# DAC.net
KiCad netlist of a schematic drawn in Altium Designer
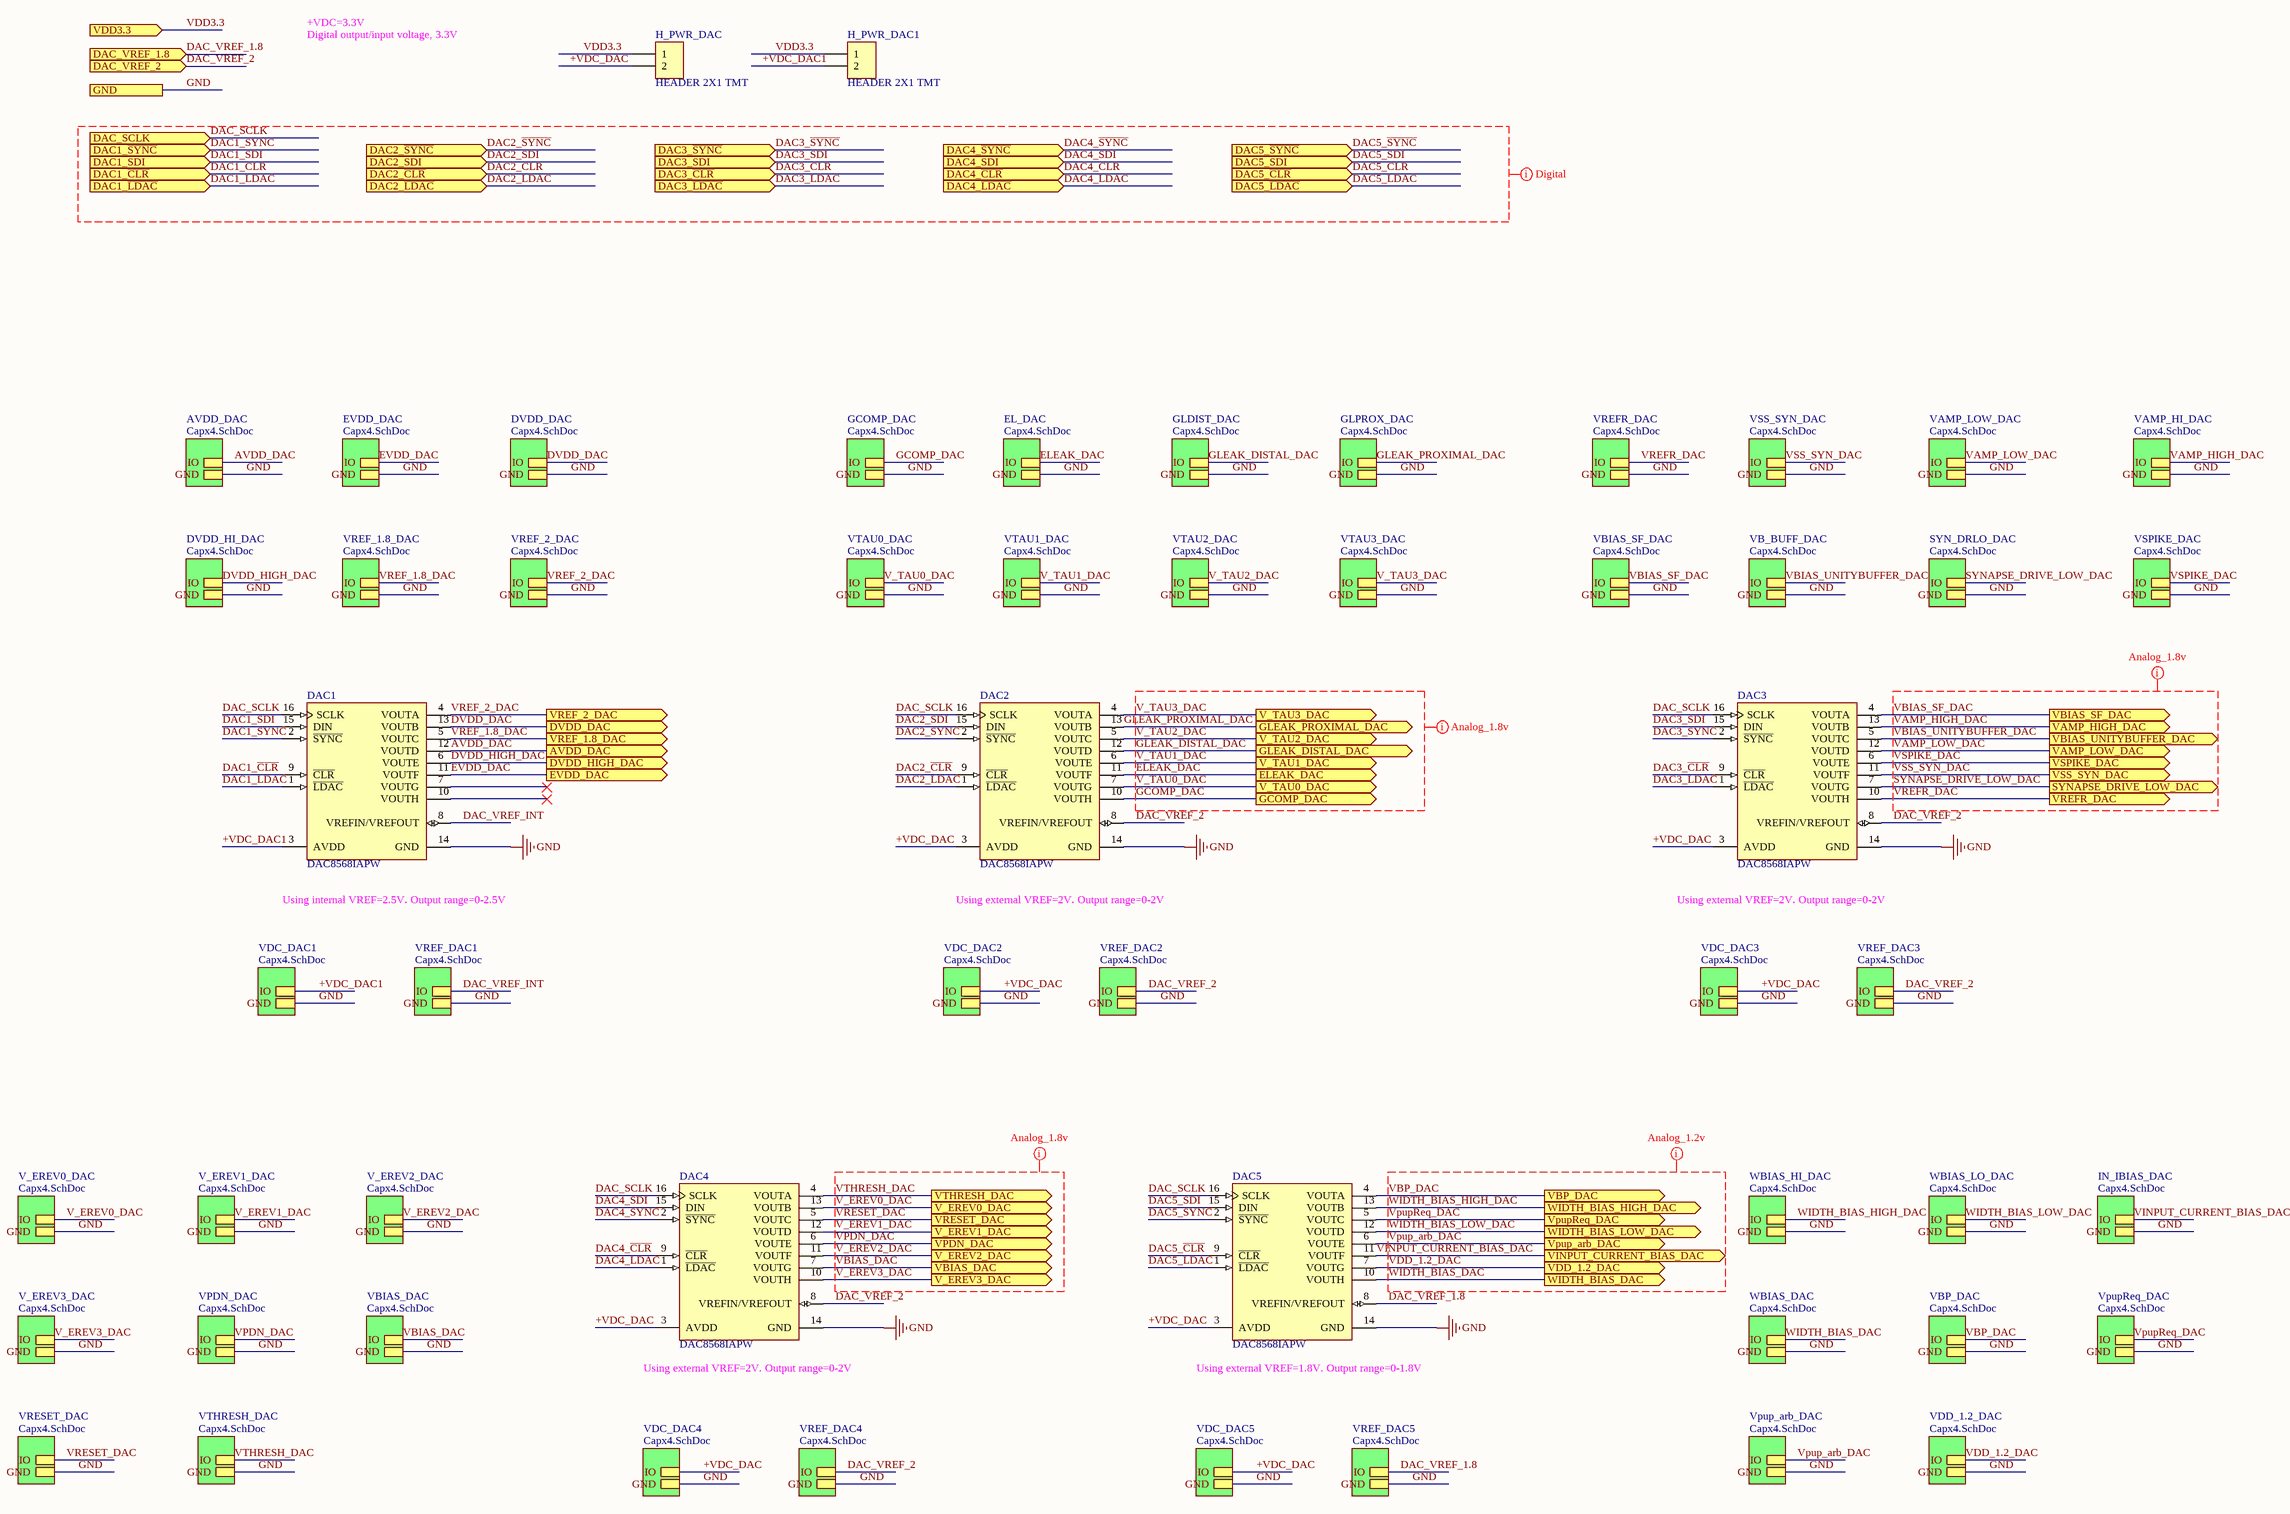
[diagram p0: DAC.SchDoc]

(export (version "E")
  (design (tool "Eeschema 10.0.6"))
  (components
    (comp (ref "DAC1")
      (value "DAC8568IAPW")
      (footprint "TI-PW16_M")
      (fields (field (name "MANUFACTURER") "Texas Instruments"))
      (libsource (lib "Altium Content Vault") (part "TI-DAC8568PW16"))
    )
    (comp (ref "DAC2")
      (value "DAC8568IAPW")
      (footprint "TI-PW16_M")
      (fields (field (name "MANUFACTURER") "Texas Instruments"))
      (libsource (lib "Altium Content Vault") (part "TI-DAC8568PW16"))
    )
    (comp (ref "DAC3")
      (value "DAC8568IAPW")
      (footprint "TI-PW16_M")
      (fields (field (name "MANUFACTURER") "Texas Instruments"))
      (libsource (lib "Altium Content Vault") (part "TI-DAC8568PW16"))
    )
    (comp (ref "DAC4")
      (value "DAC8568IAPW")
      (footprint "TI-PW16_M")
      (fields (field (name "MANUFACTURER") "Texas Instruments"))
      (libsource (lib "Altium Content Vault") (part "TI-DAC8568PW16"))
    )
    (comp (ref "DAC5")
      (value "DAC8568IAPW")
      (footprint "TI-PW16_M")
      (fields (field (name "MANUFACTURER") "Texas Instruments"))
      (libsource (lib "Altium Content Vault") (part "TI-DAC8568PW16"))
    )
    (comp (ref "H_PWR_DAC")
      (value "HEADER 2X1 TMT")
      (footprint "MRI_ADC:Samtec TSW-102-07-G-S")
      (description "CONN HEADER VERT 2POS 2.54MM\r\nConnector Header Through Hole 2 position 0.100\" (2.54mm)")
      (libsource (lib "MRI_ADC") (part "HEADER 2X1 TMT"))
    )
    (comp (ref "H_PWR_DAC1")
      (value "HEADER 2X1 TMT")
      (footprint "MRI_ADC:Samtec TSW-102-07-G-S")
      (description "CONN HEADER VERT 2POS 2.54MM\r\nConnector Header Through Hole 2 position 0.100\" (2.54mm)")
      (libsource (lib "MRI_ADC") (part "HEADER 2X1 TMT"))
    )
  )
  (nets
    (net (code "1") (name "/+VDC_DAC") (class "Default")
      (node (ref "DAC2") (pin "3") (pinfunction "AVDD_3") (pintype "power_in"))
      (node (ref "DAC3") (pin "3") (pinfunction "AVDD_3") (pintype "power_in"))
      (node (ref "DAC4") (pin "3") (pinfunction "AVDD_3") (pintype "power_in"))
      (node (ref "DAC5") (pin "3") (pinfunction "AVDD_3") (pintype "power_in"))
      (node (ref "H_PWR_DAC") (pin "2") (pinfunction "2_2") (pintype "passive"))
    )
    (net (code "2") (name "/+VDC_DAC1") (class "Default")
      (node (ref "DAC1") (pin "3") (pinfunction "AVDD_3") (pintype "power_in"))
      (node (ref "H_PWR_DAC1") (pin "2") (pinfunction "2_2") (pintype "passive"))
    )
    (net (code "3") (name "/AVDD_DAC") (class "Default")
      (node (ref "DAC1") (pin "12") (pinfunction "VOUTD_12") (pintype "tri_state"))
    )
    (net (code "4") (name "/DAC1_SDI") (class "Default")
      (node (ref "DAC1") (pin "15") (pinfunction "DIN_15") (pintype "input"))
    )
    (net (code "5") (name "/DAC1_~{CLR}") (class "Default")
      (node (ref "DAC1") (pin "9") (pinfunction "~{CLR}_9") (pintype "input"))
    )
    (net (code "6") (name "/DAC1_~{LDAC}") (class "Default")
      (node (ref "DAC1") (pin "1") (pinfunction "~{LDAC}_1") (pintype "input"))
    )
    (net (code "7") (name "/DAC1_~{SYNC}") (class "Default")
      (node (ref "DAC1") (pin "2") (pinfunction "~{SYNC}_2") (pintype "input"))
    )
    (net (code "8") (name "/DAC2_SDI") (class "Default")
      (node (ref "DAC2") (pin "15") (pinfunction "DIN_15") (pintype "input"))
    )
    (net (code "9") (name "/DAC2_~{CLR}") (class "Default")
      (node (ref "DAC2") (pin "9") (pinfunction "~{CLR}_9") (pintype "input"))
    )
    (net (code "10") (name "/DAC2_~{LDAC}") (class "Default")
      (node (ref "DAC2") (pin "1") (pinfunction "~{LDAC}_1") (pintype "input"))
    )
    (net (code "11") (name "/DAC2_~{SYNC}") (class "Default")
      (node (ref "DAC2") (pin "2") (pinfunction "~{SYNC}_2") (pintype "input"))
    )
    (net (code "12") (name "/DAC3_SDI") (class "Default")
      (node (ref "DAC3") (pin "15") (pinfunction "DIN_15") (pintype "input"))
    )
    (net (code "13") (name "/DAC3_~{CLR}") (class "Default")
      (node (ref "DAC3") (pin "9") (pinfunction "~{CLR}_9") (pintype "input"))
    )
    (net (code "14") (name "/DAC3_~{LDAC}") (class "Default")
      (node (ref "DAC3") (pin "1") (pinfunction "~{LDAC}_1") (pintype "input"))
    )
    (net (code "15") (name "/DAC3_~{SYNC}") (class "Default")
      (node (ref "DAC3") (pin "2") (pinfunction "~{SYNC}_2") (pintype "input"))
    )
    (net (code "16") (name "/DAC4_SDI") (class "Default")
      (node (ref "DAC4") (pin "15") (pinfunction "DIN_15") (pintype "input"))
    )
    (net (code "17") (name "/DAC4_~{CLR}") (class "Default")
      (node (ref "DAC4") (pin "9") (pinfunction "~{CLR}_9") (pintype "input"))
    )
    (net (code "18") (name "/DAC4_~{LDAC}") (class "Default")
      (node (ref "DAC4") (pin "1") (pinfunction "~{LDAC}_1") (pintype "input"))
    )
    (net (code "19") (name "/DAC4_~{SYNC}") (class "Default")
      (node (ref "DAC4") (pin "2") (pinfunction "~{SYNC}_2") (pintype "input"))
    )
    (net (code "20") (name "/DAC5_SDI") (class "Default")
      (node (ref "DAC5") (pin "15") (pinfunction "DIN_15") (pintype "input"))
    )
    (net (code "21") (name "/DAC5_~{CLR}") (class "Default")
      (node (ref "DAC5") (pin "9") (pinfunction "~{CLR}_9") (pintype "input"))
    )
    (net (code "22") (name "/DAC5_~{LDAC}") (class "Default")
      (node (ref "DAC5") (pin "1") (pinfunction "~{LDAC}_1") (pintype "input"))
    )
    (net (code "23") (name "/DAC5_~{SYNC}") (class "Default")
      (node (ref "DAC5") (pin "2") (pinfunction "~{SYNC}_2") (pintype "input"))
    )
    (net (code "24") (name "/DAC_SCLK") (class "Default")
      (node (ref "DAC1") (pin "16") (pinfunction "SCLK_16") (pintype "input"))
      (node (ref "DAC2") (pin "16") (pinfunction "SCLK_16") (pintype "input"))
      (node (ref "DAC3") (pin "16") (pinfunction "SCLK_16") (pintype "input"))
      (node (ref "DAC4") (pin "16") (pinfunction "SCLK_16") (pintype "input"))
      (node (ref "DAC5") (pin "16") (pinfunction "SCLK_16") (pintype "input"))
    )
    (net (code "25") (name "/DAC_VREF_1.8") (class "Default")
      (node (ref "DAC5") (pin "8") (pinfunction "VREFIN/VREFOUT_8") (pintype "bidirectional"))
    )
    (net (code "26") (name "/DAC_VREF_2") (class "Default")
      (node (ref "DAC2") (pin "8") (pinfunction "VREFIN/VREFOUT_8") (pintype "bidirectional"))
      (node (ref "DAC3") (pin "8") (pinfunction "VREFIN/VREFOUT_8") (pintype "bidirectional"))
      (node (ref "DAC4") (pin "8") (pinfunction "VREFIN/VREFOUT_8") (pintype "bidirectional"))
    )
    (net (code "27") (name "/DAC_VREF_INT") (class "Default")
      (node (ref "DAC1") (pin "8") (pinfunction "VREFIN/VREFOUT_8") (pintype "bidirectional"))
    )
    (net (code "28") (name "/DVDD_DAC") (class "Default")
      (node (ref "DAC1") (pin "13") (pinfunction "VOUTB_13") (pintype "tri_state"))
    )
    (net (code "29") (name "/DVDD_HIGH_DAC") (class "Default")
      (node (ref "DAC1") (pin "6") (pinfunction "VOUTE_6") (pintype "tri_state"))
    )
    (net (code "30") (name "/ELEAK_DAC") (class "Default")
      (node (ref "DAC2") (pin "11") (pinfunction "VOUTF_11") (pintype "tri_state"))
    )
    (net (code "31") (name "/EVDD_DAC") (class "Default")
      (node (ref "DAC1") (pin "11") (pinfunction "VOUTF_11") (pintype "tri_state"))
    )
    (net (code "32") (name "/GCOMP_DAC") (class "Default")
      (node (ref "DAC2") (pin "10") (pinfunction "VOUTH_10") (pintype "tri_state"))
    )
    (net (code "33") (name "/GLEAK_DISTAL_DAC") (class "Default")
      (node (ref "DAC2") (pin "12") (pinfunction "VOUTD_12") (pintype "tri_state"))
    )
    (net (code "34") (name "/GLEAK_PROXIMAL_DAC") (class "Default")
      (node (ref "DAC2") (pin "13") (pinfunction "VOUTB_13") (pintype "tri_state"))
    )
    (net (code "35") (name "/SYNAPSE_DRIVE_LOW_DAC") (class "Default")
      (node (ref "DAC3") (pin "7") (pinfunction "VOUTG_7") (pintype "tri_state"))
    )
    (net (code "36") (name "/VAMP_HIGH_DAC") (class "Default")
      (node (ref "DAC3") (pin "13") (pinfunction "VOUTB_13") (pintype "tri_state"))
    )
    (net (code "37") (name "/VAMP_LOW_DAC") (class "Default")
      (node (ref "DAC3") (pin "12") (pinfunction "VOUTD_12") (pintype "tri_state"))
    )
    (net (code "38") (name "/VBIAS_DAC") (class "Default")
      (node (ref "DAC4") (pin "7") (pinfunction "VOUTG_7") (pintype "tri_state"))
    )
    (net (code "39") (name "/VBIAS_SF_DAC") (class "Default")
      (node (ref "DAC3") (pin "4") (pinfunction "VOUTA_4") (pintype "tri_state"))
    )
    (net (code "40") (name "/VBIAS_UNITYBUFFER_DAC") (class "Default")
      (node (ref "DAC3") (pin "5") (pinfunction "VOUTC_5") (pintype "tri_state"))
    )
    (net (code "41") (name "/VBP_DAC") (class "Default")
      (node (ref "DAC5") (pin "4") (pinfunction "VOUTA_4") (pintype "tri_state"))
    )
    (net (code "42") (name "/VDD3.3") (class "Default")
      (node (ref "H_PWR_DAC") (pin "1") (pinfunction "1_1") (pintype "passive"))
      (node (ref "H_PWR_DAC1") (pin "1") (pinfunction "1_1") (pintype "passive"))
    )
    (net (code "43") (name "/VDD_1.2_DAC") (class "Default")
      (node (ref "DAC5") (pin "7") (pinfunction "VOUTG_7") (pintype "tri_state"))
    )
    (net (code "44") (name "/VINPUT_CURRENT_BIAS_DAC") (class "Default")
      (node (ref "DAC5") (pin "11") (pinfunction "VOUTF_11") (pintype "tri_state"))
    )
    (net (code "45") (name "/VPDN_DAC") (class "Default")
      (node (ref "DAC4") (pin "6") (pinfunction "VOUTE_6") (pintype "tri_state"))
    )
    (net (code "46") (name "/VREFR_DAC") (class "Default")
      (node (ref "DAC3") (pin "10") (pinfunction "VOUTH_10") (pintype "tri_state"))
    )
    (net (code "47") (name "/VREF_1.8_DAC") (class "Default")
      (node (ref "DAC1") (pin "5") (pinfunction "VOUTC_5") (pintype "tri_state"))
    )
    (net (code "48") (name "/VREF_2_DAC") (class "Default")
      (node (ref "DAC1") (pin "4") (pinfunction "VOUTA_4") (pintype "tri_state"))
    )
    (net (code "49") (name "/VRESET_DAC") (class "Default")
      (node (ref "DAC4") (pin "5") (pinfunction "VOUTC_5") (pintype "tri_state"))
    )
    (net (code "50") (name "/VSPIKE_DAC") (class "Default")
      (node (ref "DAC3") (pin "6") (pinfunction "VOUTE_6") (pintype "tri_state"))
    )
    (net (code "51") (name "/VSS_SYN_DAC") (class "Default")
      (node (ref "DAC3") (pin "11") (pinfunction "VOUTF_11") (pintype "tri_state"))
    )
    (net (code "52") (name "/VTHRESH_DAC") (class "Default")
      (node (ref "DAC4") (pin "4") (pinfunction "VOUTA_4") (pintype "tri_state"))
    )
    (net (code "53") (name "/V_EREV0_DAC") (class "Default")
      (node (ref "DAC4") (pin "13") (pinfunction "VOUTB_13") (pintype "tri_state"))
    )
    (net (code "54") (name "/V_EREV1_DAC") (class "Default")
      (node (ref "DAC4") (pin "12") (pinfunction "VOUTD_12") (pintype "tri_state"))
    )
    (net (code "55") (name "/V_EREV2_DAC") (class "Default")
      (node (ref "DAC4") (pin "11") (pinfunction "VOUTF_11") (pintype "tri_state"))
    )
    (net (code "56") (name "/V_EREV3_DAC") (class "Default")
      (node (ref "DAC4") (pin "10") (pinfunction "VOUTH_10") (pintype "tri_state"))
    )
    (net (code "57") (name "/V_TAU0_DAC") (class "Default")
      (node (ref "DAC2") (pin "7") (pinfunction "VOUTG_7") (pintype "tri_state"))
    )
    (net (code "58") (name "/V_TAU1_DAC") (class "Default")
      (node (ref "DAC2") (pin "6") (pinfunction "VOUTE_6") (pintype "tri_state"))
    )
    (net (code "59") (name "/V_TAU2_DAC") (class "Default")
      (node (ref "DAC2") (pin "5") (pinfunction "VOUTC_5") (pintype "tri_state"))
    )
    (net (code "60") (name "/V_TAU3_DAC") (class "Default")
      (node (ref "DAC2") (pin "4") (pinfunction "VOUTA_4") (pintype "tri_state"))
    )
    (net (code "61") (name "/VpupReq_DAC") (class "Default")
      (node (ref "DAC5") (pin "5") (pinfunction "VOUTC_5") (pintype "tri_state"))
    )
    (net (code "62") (name "/Vpup_arb_DAC") (class "Default")
      (node (ref "DAC5") (pin "6") (pinfunction "VOUTE_6") (pintype "tri_state"))
    )
    (net (code "63") (name "/WIDTH_BIAS_DAC") (class "Default")
      (node (ref "DAC5") (pin "10") (pinfunction "VOUTH_10") (pintype "tri_state"))
    )
    (net (code "64") (name "/WIDTH_BIAS_HIGH_DAC") (class "Default")
      (node (ref "DAC5") (pin "13") (pinfunction "VOUTB_13") (pintype "tri_state"))
    )
    (net (code "65") (name "/WIDTH_BIAS_LOW_DAC") (class "Default")
      (node (ref "DAC5") (pin "12") (pinfunction "VOUTD_12") (pintype "tri_state"))
    )
    (net (code "66") (name "GND") (class "Default")
      (node (ref "DAC1") (pin "14") (pinfunction "GND_14") (pintype "power_in"))
      (node (ref "DAC2") (pin "14") (pinfunction "GND_14") (pintype "power_in"))
      (node (ref "DAC3") (pin "14") (pinfunction "GND_14") (pintype "power_in"))
      (node (ref "DAC4") (pin "14") (pinfunction "GND_14") (pintype "power_in"))
      (node (ref "DAC5") (pin "14") (pinfunction "GND_14") (pintype "power_in"))
    )
    (net (code "67") (name "unconnected-(DAC1-VOUTG-Pad7)") (class "Default")
      (node (ref "DAC1") (pin "7") (pinfunction "VOUTG_7") (pintype "tri_state+no_connect"))
    )
    (net (code "68") (name "unconnected-(DAC1-VOUTH-Pad10)") (class "Default")
      (node (ref "DAC1") (pin "10") (pinfunction "VOUTH_10") (pintype "tri_state+no_connect"))
    )
  )
)
